# Power.net
KiCad netlist of a schematic drawn in Altium Designer
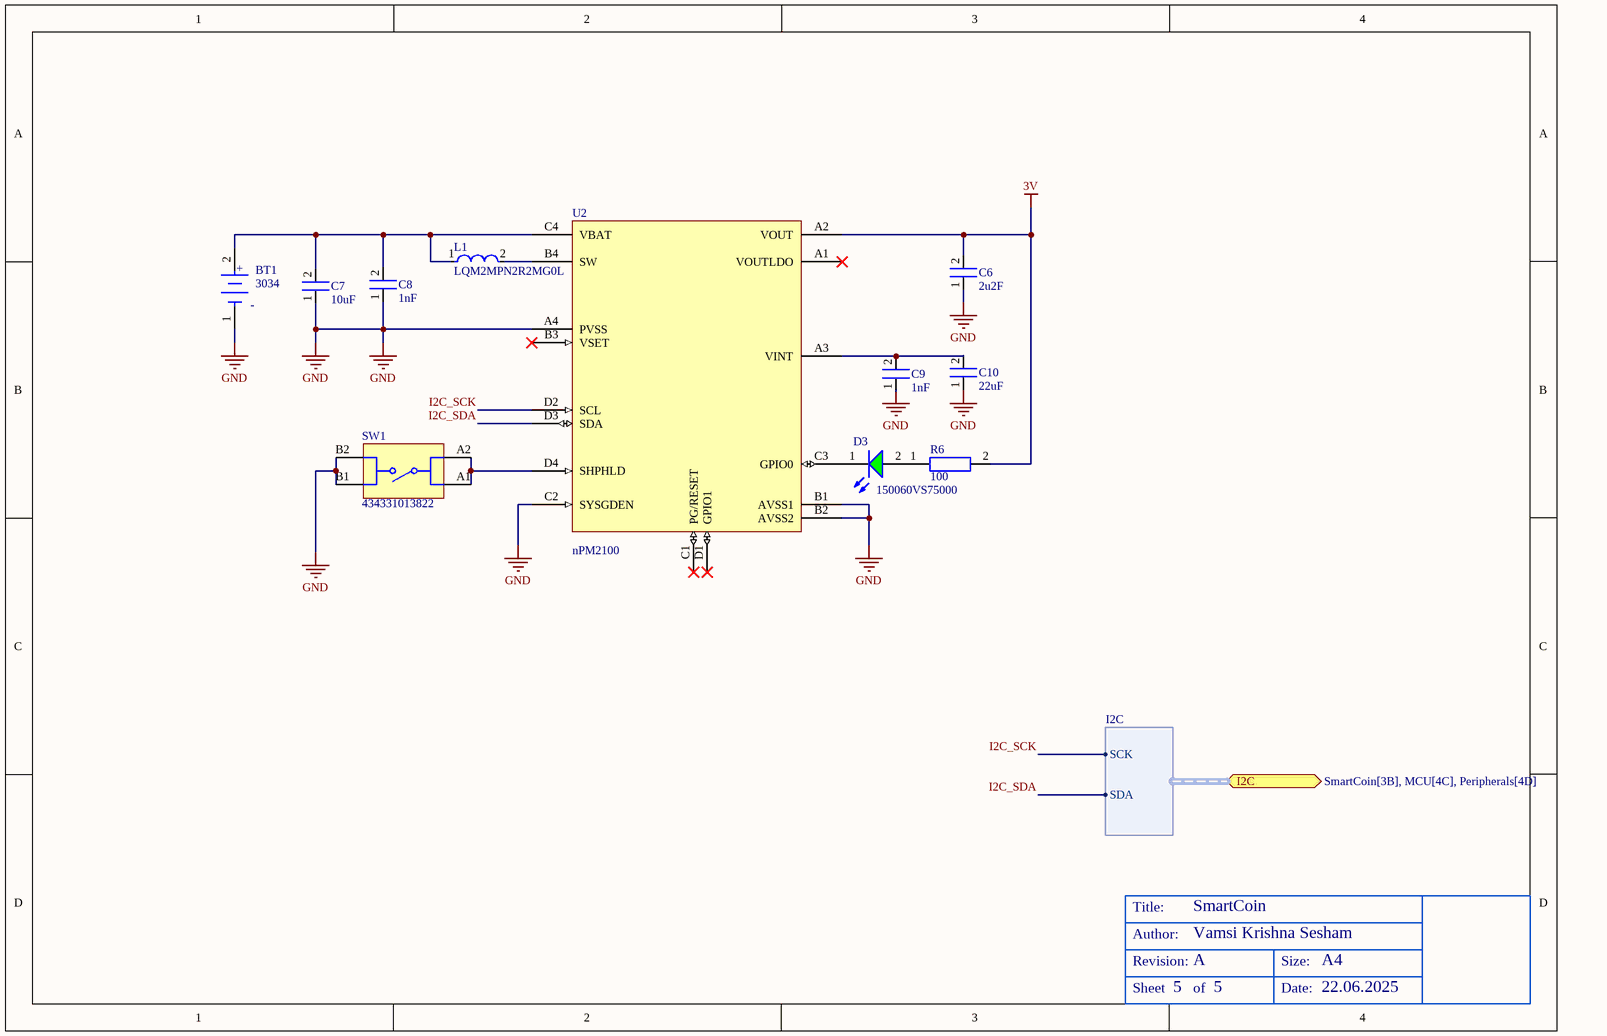
[diagram p0: Power.SchDoc]

(export (version "E")
  (design (tool "Eeschema 10.0.6"))
  (components
    (comp (ref "BT1")
      (value "3034")
      (footprint "FP-3034-MFG")
      (description "BATTERY RETAINER COIN 20MM SMD")
      (fields
        (field (name "OCTOPART") "https://octopart.com/3034-keystone-27554462")
        (field (name "MANUFACTURER") "Keystone Electronics")
      )
      (libsource (lib "Altium Content Vault") (part "60d3b5b901a8747834971d0eb8cf3fd"))
    )
    (comp (ref "C6")
      (value "2u2F")
      (footprint "Capacitor - 0201")
      (libsource (lib "SmartCoin") (part "Capacitor - 0201"))
    )
    (comp (ref "C7")
      (value "10uF")
      (footprint "Capacitor - 0402")
      (libsource (lib "SmartCoin") (part "Capacitor - 0402"))
    )
    (comp (ref "C8")
      (value "1nF")
      (footprint "Capacitor - 0201")
      (libsource (lib "SmartCoin") (part "Capacitor - 0201"))
    )
    (comp (ref "C9")
      (value "1nF")
      (footprint "Capacitor - 0201")
      (libsource (lib "SmartCoin") (part "Capacitor - 0201"))
    )
    (comp (ref "C10")
      (value "22uF")
      (footprint "Capacitor - 0402")
      (libsource (lib "SmartCoin") (part "Capacitor - 0402"))
    )
    (comp (ref "D3")
      (value "150060VS75000")
      (footprint "WL-SMCW_0603_150060xx75000")
      (description "WURTH ELEKTRONIK - 150060VS75000 - LED, Green, SMD, 0603, 30 mA, 2 V, 570 nm")
      (libsource (lib "Altium Content Vault") (part "LED_Green_2A-1K"))
    )
    (comp (ref "L1")
      (value "LQM2MPN2R2MG0L")
      (footprint "FP-LQM2MPN_G0-IPC_A")
      (description "Multilayer Type Inductor for Power Lines, 0806 (2016), 2.2μH, 20%, 0.138Ω, 1.2A")
      (fields (field (name "TOLERANCE") "20%"))
      (libsource (lib "Altium Content Vault") (part "725321dda6339637d4d059423bc1c3c"))
    )
    (comp (ref "R6")
      (value "100")
      (footprint "Resistor - 0201")
      (libsource (lib "SmartCoin") (part "Resistor - 0201"))
    )
    (comp (ref "SW1")
      (value "434331013822")
      (footprint "434331013822")
      (description "434331013822 Tactile Switch, 0.05A, 12Vdc, 220Gf, Smd Rohs Compliant: Yes")
      (libsource (lib "Altium Content Vault") (part "SPST-NO_4P"))
    )
    (comp (ref "U2") (value "nPM2100") (footprint "npm2100") (libsource (lib "SmartCoin") (part "nPM2100")))
  )
  (nets
    (net (code "2") (name "/I2C_SCK") (class "Default")
      (node (ref "U2") (pin "D2") (pinfunction "SCL_D2") (pintype "input"))
    )
    (net (code "3") (name "/I2C_SDA") (class "Default")
      (node (ref "U2") (pin "D3") (pinfunction "SDA_D3") (pintype "bidirectional"))
    )
    (net (code "5") (name "3V") (class "Default")
      (node (ref "C6") (pin "2") (pintype "passive"))
      (node (ref "R6") (pin "2") (pintype "passive"))
      (node (ref "U2") (pin "A2") (pinfunction "VOUT_A2") (pintype "power_in"))
    )
    (net (code "6") (name "GND") (class "Default")
      (node (ref "BT1") (pin "1") (pinfunction "C_1") (pintype "passive"))
      (node (ref "C10") (pin "1") (pintype "passive"))
      (node (ref "C6") (pin "1") (pintype "passive"))
      (node (ref "C7") (pin "1") (pintype "passive"))
      (node (ref "C8") (pin "1") (pintype "passive"))
      (node (ref "C9") (pin "1") (pintype "passive"))
      (node (ref "SW1") (pin "B1") (pinfunction "B1_B1") (pintype "passive"))
      (node (ref "SW1") (pin "B2") (pinfunction "B2_B2") (pintype "passive"))
      (node (ref "U2") (pin "A4") (pinfunction "PVSS_A4") (pintype "power_in"))
      (node (ref "U2") (pin "B1") (pinfunction "AVSS1_B1") (pintype "power_in"))
      (node (ref "U2") (pin "B2") (pinfunction "AVSS2_B2") (pintype "power_in"))
      (node (ref "U2") (pin "C2") (pinfunction "SYSGDEN_C2") (pintype "input"))
    )
    (net (code "7") (name "Net-(BT1-A)") (class "Default")
      (node (ref "BT1") (pin "2") (pinfunction "A_2") (pintype "passive"))
      (node (ref "C7") (pin "2") (pintype "passive"))
      (node (ref "C8") (pin "2") (pintype "passive"))
      (node (ref "L1") (pin "1") (pinfunction "1_1") (pintype "passive"))
      (node (ref "U2") (pin "C4") (pinfunction "VBAT_C4") (pintype "power_in"))
    )
    (net (code "8") (name "Net-(D3-A)") (class "Default")
      (node (ref "D3") (pin "2") (pinfunction "A_2") (pintype "passive"))
      (node (ref "R6") (pin "1") (pintype "passive"))
    )
    (net (code "9") (name "Net-(D3-K)") (class "Default")
      (node (ref "D3") (pin "1") (pinfunction "K_1") (pintype "passive"))
      (node (ref "U2") (pin "C3") (pinfunction "GPIO0_C3") (pintype "bidirectional"))
    )
    (net (code "10") (name "Net-(U2-SHPHLD)") (class "Default")
      (node (ref "SW1") (pin "A1") (pinfunction "A1_A1") (pintype "passive"))
      (node (ref "SW1") (pin "A2") (pinfunction "A2_A2") (pintype "passive"))
      (node (ref "U2") (pin "D4") (pinfunction "SHPHLD_D4") (pintype "input"))
    )
    (net (code "11") (name "Net-(U2-SW)") (class "Default")
      (node (ref "L1") (pin "2") (pinfunction "2_2") (pintype "passive"))
      (node (ref "U2") (pin "B4") (pinfunction "SW_B4") (pintype "power_in"))
    )
    (net (code "12") (name "Net-(U2-VINT)") (class "Default")
      (node (ref "C10") (pin "2") (pintype "passive"))
      (node (ref "C9") (pin "2") (pintype "passive"))
      (node (ref "U2") (pin "A3") (pinfunction "VINT_A3") (pintype "power_in"))
    )
    (net (code "13") (name "unconnected-(U2-GPIO1-PadD1)") (class "Default")
      (node (ref "U2") (pin "D1") (pinfunction "GPIO1_D1") (pintype "bidirectional+no_connect"))
    )
    (net (code "14") (name "unconnected-(U2-PG{slash}RESET-PadC1)") (class "Default")
      (node (ref "U2") (pin "C1") (pinfunction "PG/RESET_C1") (pintype "bidirectional+no_connect"))
    )
    (net (code "15") (name "unconnected-(U2-VOUTLDO-PadA1)") (class "Default")
      (node (ref "U2") (pin "A1") (pinfunction "VOUTLDO_A1") (pintype "power_in+no_connect"))
    )
    (net (code "16") (name "unconnected-(U2-VSET-PadB3)") (class "Default")
      (node (ref "U2") (pin "B3") (pinfunction "VSET_B3") (pintype "input+no_connect"))
    )
  )
)
